# PIN2DMD-v3_0.net
KiCad netlist of a schematic drawn in EAGLE
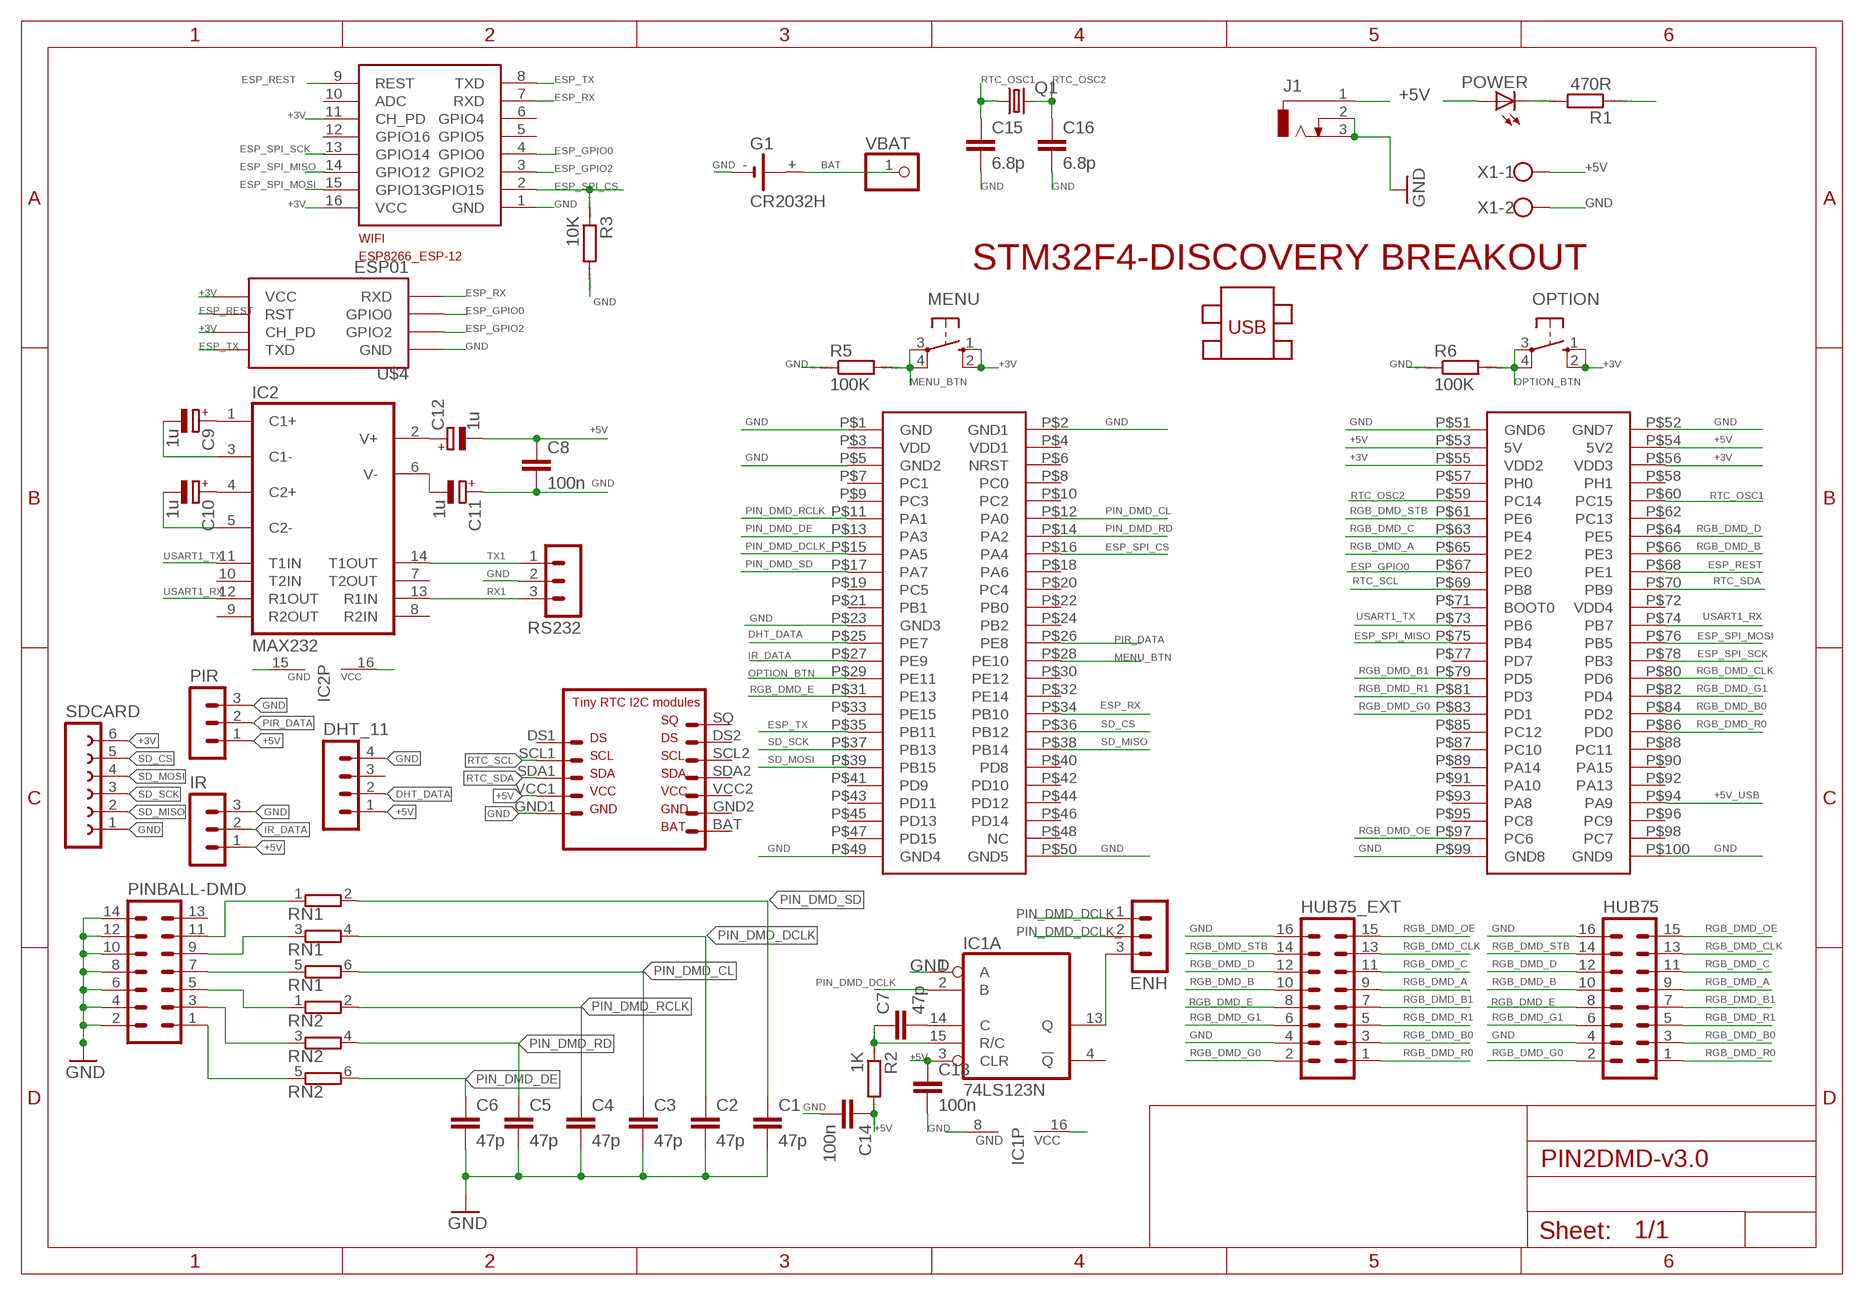
[diagram p0: schematic, sheet 1]

(export (version "E")
  (design (tool "Eeschema 10.0.6"))
  (components
    (comp (ref "C1")
      (value "47p")
      (footprint "eagle-import:C025-024X044")
      (libsource (lib "eagle-import") (part "C-EU025-024X044"))
    )
    (comp (ref "C2")
      (value "47p")
      (footprint "eagle-import:C025-024X044")
      (libsource (lib "eagle-import") (part "C-EU025-024X044"))
    )
    (comp (ref "C3")
      (value "47p")
      (footprint "eagle-import:C025-024X044")
      (libsource (lib "eagle-import") (part "C-EU025-024X044"))
    )
    (comp (ref "C4")
      (value "47p")
      (footprint "eagle-import:C025-024X044")
      (libsource (lib "eagle-import") (part "C-EU025-024X044"))
    )
    (comp (ref "C5")
      (value "47p")
      (footprint "eagle-import:C025-024X044")
      (libsource (lib "eagle-import") (part "C-EU025-024X044"))
    )
    (comp (ref "C6")
      (value "47p")
      (footprint "eagle-import:C025-024X044")
      (libsource (lib "eagle-import") (part "C-EU025-024X044"))
    )
    (comp (ref "C7")
      (value "47p")
      (footprint "eagle-import:C025-024X044")
      (libsource (lib "eagle-import") (part "C-EU025-024X044"))
    )
    (comp (ref "C8")
      (value "100n")
      (footprint "eagle-import:C025-024X044")
      (libsource (lib "eagle-import") (part "C-EU025-024X044"))
    )
    (comp (ref "C9")
      (value "1u")
      (footprint "eagle-import:E2-4")
      (libsource (lib "eagle-import") (part "CPOL-EUE2-4"))
    )
    (comp (ref "C10")
      (value "1u")
      (footprint "eagle-import:E2-4")
      (libsource (lib "eagle-import") (part "CPOL-EUE2-4"))
    )
    (comp (ref "C11")
      (value "1u")
      (footprint "eagle-import:E2-4")
      (libsource (lib "eagle-import") (part "CPOL-EUE2-4"))
    )
    (comp (ref "C12")
      (value "1u")
      (footprint "eagle-import:E2-4")
      (libsource (lib "eagle-import") (part "CPOL-EUE2-4"))
    )
    (comp (ref "C13")
      (value "100n")
      (footprint "eagle-import:C025-024X044")
      (libsource (lib "eagle-import") (part "C-EU025-024X044"))
    )
    (comp (ref "C14")
      (value "100n")
      (footprint "eagle-import:C025-024X044")
      (libsource (lib "eagle-import") (part "C-EU025-024X044"))
    )
    (comp (ref "C15")
      (value "6.8p")
      (footprint "eagle-import:C025-024X044")
      (libsource (lib "eagle-import") (part "C-EU025-024X044"))
    )
    (comp (ref "C16")
      (value "6.8p")
      (footprint "eagle-import:C025-024X044")
      (libsource (lib "eagle-import") (part "C-EU025-024X044"))
    )
    (comp (ref "DHT_11")
      (value "MA04-1")
      (footprint "eagle-import:MA04-1")
      (libsource (lib "eagle-import") (part "MA04-1"))
    )
    (comp (ref "ENH")
      (value "MA03-1")
      (footprint "eagle-import:MA03-1")
      (libsource (lib "eagle-import") (part "MA03-1"))
    )
    (comp (ref "G1")
      (value "CR2032H")
      (footprint "eagle-import:CR2032H")
      (libsource (lib "eagle-import") (part "CR2032H"))
    )
    (comp (ref "HUB75")
      (value "MA08-2")
      (footprint "eagle-import:MA08-2")
      (libsource (lib "eagle-import") (part "MA08-2"))
    )
    (comp (ref "HUB75_EXT")
      (value "MA08-2")
      (footprint "eagle-import:MA08-2")
      (libsource (lib "eagle-import") (part "MA08-2"))
    )
    (comp (ref "IC1")
      (value "74LS123N")
      (footprint "eagle-import:DIL16")
      (libsource (lib "eagle-import") (part "74123NLS"))
    )
    (comp (ref "IC2")
      (value "MAX232")
      (footprint "eagle-import:DIL16")
      (fields (field (name "MF") "MAXIM") (field (name "MPN") "MAX232ACPE+"))
      (libsource (lib "eagle-import") (part "MAX232"))
    )
    (comp (ref "IR")
      (value "MA03-1")
      (footprint "eagle-import:MA03-1")
      (libsource (lib "eagle-import") (part "MA03-1"))
    )
    (comp (ref "J1")
      (value "DCJ0303")
      (footprint "eagle-import:DCJ0303")
      (libsource (lib "eagle-import") (part "DCJ0303"))
    )
    (comp (ref "MENU")
      (value "10-XX")
      (footprint "eagle-import:B3F-10XX")
      (fields (field (name "MPN") "B3F-1000"))
      (libsource (lib "eagle-import") (part "10-XX"))
    )
    (comp (ref "OPTION")
      (value "10-XX")
      (footprint "eagle-import:B3F-10XX")
      (fields (field (name "MPN") "B3F-1000"))
      (libsource (lib "eagle-import") (part "10-XX"))
    )
    (comp (ref "PINBALL-DMD")
      (value "MA07-2")
      (footprint "eagle-import:MA07-2")
      (libsource (lib "eagle-import") (part "MA07-2"))
    )
    (comp (ref "PIR")
      (value "MA03-1")
      (footprint "eagle-import:MA03-1")
      (libsource (lib "eagle-import") (part "MA03-1"))
    )
    (comp (ref "POWER")
      (value "LED3MM")
      (footprint "eagle-import:LED3MM")
      (libsource (lib "eagle-import") (part "LED3MM"))
    )
    (comp (ref "Q1")
      (value "CRYSTALTC38H")
      (footprint "eagle-import:TC38H")
      (libsource (lib "eagle-import") (part "CRYSTALTC38H"))
    )
    (comp (ref "R1")
      (value "470R")
      (footprint "eagle-import:0207_10")
      (libsource (lib "eagle-import") (part "R0207/10"))
    )
    (comp (ref "R2")
      (value "1K")
      (footprint "eagle-import:0207_10")
      (libsource (lib "eagle-import") (part "R0207/10"))
    )
    (comp (ref "R3")
      (value "10K")
      (footprint "eagle-import:0207_10")
      (libsource (lib "eagle-import") (part "R0207/10"))
    )
    (comp (ref "R5")
      (value "100K")
      (footprint "eagle-import:0207_10")
      (libsource (lib "eagle-import") (part "R0207/10"))
    )
    (comp (ref "R6")
      (value "100K")
      (footprint "eagle-import:0207_10")
      (libsource (lib "eagle-import") (part "R0207/10"))
    )
    (comp (ref "RN1")
      (value "E3RP")
      (footprint "eagle-import:SIL6")
      (libsource (lib "eagle-import") (part "E3RP"))
    )
    (comp (ref "RN2")
      (value "E3RP")
      (footprint "eagle-import:SIL6")
      (libsource (lib "eagle-import") (part "E3RP"))
    )
    (comp (ref "RS232")
      (value "MA03-1")
      (footprint "eagle-import:MA03-1")
      (libsource (lib "eagle-import") (part "MA03-1"))
    )
    (comp (ref "SDCARD")
      (value "FE06-1")
      (footprint "eagle-import:FE06")
      (libsource (lib "eagle-import") (part "FE06-1"))
    )
    (comp (ref "U$1")
      (value "STM32F4-DISCOVERY")
      (footprint "eagle-import:STM32F4-DISCOVERY")
      (libsource (lib "eagle-import") (part "STM32F4-DISCOVERY"))
    )
    (comp (ref "U$3")
      (value "RTC")
      (footprint "eagle-import:RTC")
      (libsource (lib "eagle-import") (part "RTC"))
    )
    (comp (ref "U$4")
      (value "ESP01")
      (footprint "eagle-import:ESP01")
      (libsource (lib "eagle-import") (part "ESP01"))
    )
    (comp (ref "VBAT")
      (value "PINHD-1X1")
      (footprint "eagle-import:1X01")
      (libsource (lib "eagle-import") (part "PINHD-1X1"))
    )
    (comp (ref "WIFI")
      (value "ESP8266_ESP-12")
      (footprint "eagle-import:ESP8266-ESP12")
      (libsource (lib "eagle-import") (part "ESP8266_ESP-12"))
    )
    (comp (ref "X1")
      (value "W237-102")
      (footprint "eagle-import:W237-102")
      (fields (field (name "MPN") "237-102"))
      (libsource (lib "eagle-import") (part "W237-102"))
    )
  )
  (nets
    (net (code "1") (name "+3V") (class "Default")
      (node (ref "MENU") (pin "1") (pinfunction "S_1") (pintype "passive"))
      (node (ref "MENU") (pin "2") (pinfunction "S1_2") (pintype "passive"))
      (node (ref "OPTION") (pin "1") (pinfunction "S_1") (pintype "passive"))
      (node (ref "OPTION") (pin "2") (pinfunction "S1_2") (pintype "passive"))
      (node (ref "SDCARD") (pin "6") (pinfunction "6_6") (pintype "passive"))
      (node (ref "U$1") (pin "P$55") (pinfunction "VDD2_P$55") (pintype "bidirectional"))
      (node (ref "U$1") (pin "P$56") (pinfunction "VDD3_P$56") (pintype "bidirectional"))
      (node (ref "U$4") (pin "CH_PD") (pinfunction "CH_PD_CH_PD") (pintype "bidirectional"))
      (node (ref "U$4") (pin "VCC") (pinfunction "VCC_VCC") (pintype "bidirectional"))
      (node (ref "WIFI") (pin "11") (pinfunction "CH_PD_11") (pintype "bidirectional"))
      (node (ref "WIFI") (pin "16") (pinfunction "VCC_16") (pintype "bidirectional"))
    )
    (net (code "2") (name "+5V") (class "Default")
      (node (ref "C12") (pin "-") (pinfunction "-_-") (pintype "passive"))
      (node (ref "C13") (pin "1") (pinfunction "1_1") (pintype "passive"))
      (node (ref "C14") (pin "1") (pinfunction "1_1") (pintype "passive"))
      (node (ref "C8") (pin "1") (pinfunction "1_1") (pintype "passive"))
      (node (ref "DHT_11") (pin "1") (pinfunction "1_1") (pintype "passive"))
      (node (ref "IC1") (pin "16") (pinfunction "VCC_16") (pintype "power_in"))
      (node (ref "IC1") (pin "3") (pinfunction "CLR_3") (pintype "input"))
      (node (ref "IC2") (pin "16") (pinfunction "VCC_16") (pintype "power_in"))
      (node (ref "IR") (pin "1") (pinfunction "1_1") (pintype "passive"))
      (node (ref "J1") (pin "1") (pinfunction "1_1") (pintype "passive"))
      (node (ref "PIR") (pin "1") (pinfunction "1_1") (pintype "passive"))
      (node (ref "POWER") (pin "A") (pinfunction "A_A") (pintype "passive"))
      (node (ref "R2") (pin "2") (pinfunction "2_2") (pintype "passive"))
      (node (ref "U$1") (pin "P$53") (pinfunction "5V_P$53") (pintype "bidirectional"))
      (node (ref "U$1") (pin "P$54") (pinfunction "5V2_P$54") (pintype "bidirectional"))
      (node (ref "U$3") (pin "VCC1") (pinfunction "VCC1_VCC1") (pintype "passive"))
      (node (ref "X1") (pin "1") (pinfunction "KL_1") (pintype "passive"))
    )
    (net (code "3") (name "/+5V_USB") (class "Default")
      (node (ref "U$1") (pin "P$94") (pinfunction "PA9_P$94") (pintype "bidirectional"))
    )
    (net (code "4") (name "/BAT") (class "Default")
      (node (ref "G1") (pin "+") (pinfunction "+_+") (pintype "passive"))
      (node (ref "VBAT") (pin "1") (pinfunction "1_1") (pintype "passive"))
    )
    (net (code "5") (name "/ESP_GPIO0") (class "Default")
      (node (ref "U$1") (pin "P$67") (pinfunction "PE0_P$67") (pintype "bidirectional"))
      (node (ref "U$4") (pin "GPIO0") (pinfunction "GPIO0_GPIO0") (pintype "bidirectional"))
      (node (ref "WIFI") (pin "4") (pinfunction "GPIO0_4") (pintype "bidirectional"))
    )
    (net (code "6") (name "/ESP_GPIO2") (class "Default")
      (node (ref "U$4") (pin "GPIO2") (pinfunction "GPIO2_GPIO2") (pintype "bidirectional"))
      (node (ref "WIFI") (pin "3") (pinfunction "GPIO2_3") (pintype "bidirectional"))
    )
    (net (code "7") (name "/ESP_REST") (class "Default")
      (node (ref "U$1") (pin "P$68") (pinfunction "PE1_P$68") (pintype "bidirectional"))
      (node (ref "U$4") (pin "RST") (pinfunction "RST_RST") (pintype "bidirectional"))
      (node (ref "WIFI") (pin "9") (pinfunction "REST_9") (pintype "bidirectional"))
    )
    (net (code "8") (name "/ESP_RX") (class "Default")
      (node (ref "U$1") (pin "P$34") (pinfunction "PB10_P$34") (pintype "bidirectional"))
      (node (ref "U$4") (pin "RX") (pinfunction "RXD_RX") (pintype "bidirectional"))
      (node (ref "WIFI") (pin "7") (pinfunction "RXD_7") (pintype "bidirectional"))
    )
    (net (code "9") (name "/ESP_SPI_CS") (class "Default")
      (node (ref "R3") (pin "1") (pinfunction "1_1") (pintype "passive"))
      (node (ref "U$1") (pin "P$16") (pinfunction "PA4_P$16") (pintype "bidirectional"))
      (node (ref "WIFI") (pin "2") (pinfunction "GPIO15_2") (pintype "bidirectional"))
    )
    (net (code "10") (name "/ESP_SPI_MISO") (class "Default")
      (node (ref "U$1") (pin "P$75") (pinfunction "PB4_P$75") (pintype "bidirectional"))
      (node (ref "WIFI") (pin "14") (pinfunction "GPIO12_14") (pintype "bidirectional"))
    )
    (net (code "11") (name "/ESP_SPI_MOSI") (class "Default")
      (node (ref "U$1") (pin "P$76") (pinfunction "PB5_P$76") (pintype "bidirectional"))
      (node (ref "WIFI") (pin "15") (pinfunction "GPIO13_15") (pintype "bidirectional"))
    )
    (net (code "12") (name "/ESP_SPI_SCK") (class "Default")
      (node (ref "U$1") (pin "P$78") (pinfunction "PB3_P$78") (pintype "bidirectional"))
      (node (ref "WIFI") (pin "13") (pinfunction "GPIO14_13") (pintype "bidirectional"))
    )
    (net (code "13") (name "/ESP_TX") (class "Default")
      (node (ref "U$1") (pin "P$35") (pinfunction "PB11_P$35") (pintype "bidirectional"))
      (node (ref "U$4") (pin "TX") (pinfunction "TXD_TX") (pintype "bidirectional"))
      (node (ref "WIFI") (pin "8") (pinfunction "TXD_8") (pintype "bidirectional"))
    )
    (net (code "14") (name "/MENU_BTN") (class "Default")
      (node (ref "MENU") (pin "3") (pinfunction "P_3") (pintype "passive"))
      (node (ref "MENU") (pin "4") (pinfunction "P1_4") (pintype "passive"))
      (node (ref "R5") (pin "2") (pinfunction "2_2") (pintype "passive"))
      (node (ref "U$1") (pin "P$28") (pinfunction "PE10_P$28") (pintype "bidirectional"))
    )
    (net (code "15") (name "/OPTION_BTN") (class "Default")
      (node (ref "OPTION") (pin "3") (pinfunction "P_3") (pintype "passive"))
      (node (ref "OPTION") (pin "4") (pinfunction "P1_4") (pintype "passive"))
      (node (ref "R6") (pin "2") (pinfunction "2_2") (pintype "passive"))
      (node (ref "U$1") (pin "P$29") (pinfunction "PE11_P$29") (pintype "bidirectional"))
    )
    (net (code "16") (name "/PIN_DMD_DCLK_") (class "Default")
      (node (ref "ENH") (pin "2") (pinfunction "2_2") (pintype "passive"))
      (node (ref "U$1") (pin "P$15") (pinfunction "PA5_P$15") (pintype "bidirectional"))
    )
    (net (code "17") (name "/RGB_DMD_A") (class "Default")
      (node (ref "HUB75") (pin "9") (pinfunction "9_9") (pintype "passive"))
      (node (ref "HUB75_EXT") (pin "9") (pinfunction "9_9") (pintype "passive"))
      (node (ref "U$1") (pin "P$65") (pinfunction "PE2_P$65") (pintype "bidirectional"))
    )
    (net (code "18") (name "/RGB_DMD_B") (class "Default")
      (node (ref "HUB75") (pin "10") (pinfunction "10_10") (pintype "passive"))
      (node (ref "HUB75_EXT") (pin "10") (pinfunction "10_10") (pintype "passive"))
      (node (ref "U$1") (pin "P$66") (pinfunction "PE3_P$66") (pintype "bidirectional"))
    )
    (net (code "19") (name "/RGB_DMD_B0") (class "Default")
      (node (ref "HUB75") (pin "3") (pinfunction "3_3") (pintype "passive"))
      (node (ref "HUB75_EXT") (pin "3") (pinfunction "3_3") (pintype "passive"))
      (node (ref "U$1") (pin "P$84") (pinfunction "PD2_P$84") (pintype "bidirectional"))
    )
    (net (code "20") (name "/RGB_DMD_B1") (class "Default")
      (node (ref "HUB75") (pin "7") (pinfunction "7_7") (pintype "passive"))
      (node (ref "HUB75_EXT") (pin "7") (pinfunction "7_7") (pintype "passive"))
      (node (ref "U$1") (pin "P$79") (pinfunction "PD5_P$79") (pintype "bidirectional"))
    )
    (net (code "21") (name "/RGB_DMD_C") (class "Default")
      (node (ref "HUB75") (pin "11") (pinfunction "11_11") (pintype "passive"))
      (node (ref "HUB75_EXT") (pin "11") (pinfunction "11_11") (pintype "passive"))
      (node (ref "U$1") (pin "P$63") (pinfunction "PE4_P$63") (pintype "bidirectional"))
    )
    (net (code "22") (name "/RGB_DMD_CLK") (class "Default")
      (node (ref "HUB75") (pin "13") (pinfunction "13_13") (pintype "passive"))
      (node (ref "HUB75_EXT") (pin "13") (pinfunction "13_13") (pintype "passive"))
      (node (ref "U$1") (pin "P$80") (pinfunction "PD6_P$80") (pintype "bidirectional"))
    )
    (net (code "23") (name "/RGB_DMD_D") (class "Default")
      (node (ref "HUB75") (pin "12") (pinfunction "12_12") (pintype "passive"))
      (node (ref "HUB75_EXT") (pin "12") (pinfunction "12_12") (pintype "passive"))
      (node (ref "U$1") (pin "P$64") (pinfunction "PE5_P$64") (pintype "bidirectional"))
    )
    (net (code "24") (name "/RGB_DMD_E") (class "Default")
      (node (ref "HUB75") (pin "8") (pinfunction "8_8") (pintype "passive"))
      (node (ref "HUB75_EXT") (pin "8") (pinfunction "8_8") (pintype "passive"))
      (node (ref "U$1") (pin "P$31") (pinfunction "PE13_P$31") (pintype "bidirectional"))
    )
    (net (code "25") (name "/RGB_DMD_G0") (class "Default")
      (node (ref "HUB75") (pin "2") (pinfunction "2_2") (pintype "passive"))
      (node (ref "HUB75_EXT") (pin "2") (pinfunction "2_2") (pintype "passive"))
      (node (ref "U$1") (pin "P$83") (pinfunction "PD1_P$83") (pintype "bidirectional"))
    )
    (net (code "26") (name "/RGB_DMD_G1") (class "Default")
      (node (ref "HUB75") (pin "6") (pinfunction "6_6") (pintype "passive"))
      (node (ref "HUB75_EXT") (pin "6") (pinfunction "6_6") (pintype "passive"))
      (node (ref "U$1") (pin "P$82") (pinfunction "PD4_P$82") (pintype "bidirectional"))
    )
    (net (code "27") (name "/RGB_DMD_OE") (class "Default")
      (node (ref "HUB75") (pin "15") (pinfunction "15_15") (pintype "passive"))
      (node (ref "HUB75_EXT") (pin "15") (pinfunction "15_15") (pintype "passive"))
      (node (ref "U$1") (pin "P$97") (pinfunction "PC6_P$97") (pintype "bidirectional"))
    )
    (net (code "28") (name "/RGB_DMD_R0") (class "Default")
      (node (ref "HUB75") (pin "1") (pinfunction "1_1") (pintype "passive"))
      (node (ref "HUB75_EXT") (pin "1") (pinfunction "1_1") (pintype "passive"))
      (node (ref "U$1") (pin "P$86") (pinfunction "PD0_P$86") (pintype "bidirectional"))
    )
    (net (code "29") (name "/RGB_DMD_R1") (class "Default")
      (node (ref "HUB75") (pin "5") (pinfunction "5_5") (pintype "passive"))
      (node (ref "HUB75_EXT") (pin "5") (pinfunction "5_5") (pintype "passive"))
      (node (ref "U$1") (pin "P$81") (pinfunction "PD3_P$81") (pintype "bidirectional"))
    )
    (net (code "30") (name "/RGB_DMD_STB") (class "Default")
      (node (ref "HUB75") (pin "14") (pinfunction "14_14") (pintype "passive"))
      (node (ref "HUB75_EXT") (pin "14") (pinfunction "14_14") (pintype "passive"))
      (node (ref "U$1") (pin "P$61") (pinfunction "PE6_P$61") (pintype "bidirectional"))
    )
    (net (code "31") (name "/RTC_OSC1") (class "Default")
      (node (ref "C15") (pin "1") (pinfunction "1_1") (pintype "passive"))
      (node (ref "Q1") (pin "1") (pinfunction "1_1") (pintype "passive"))
      (node (ref "U$1") (pin "P$60") (pinfunction "PC15_P$60") (pintype "bidirectional"))
    )
    (net (code "32") (name "/RTC_OSC2") (class "Default")
      (node (ref "C16") (pin "1") (pinfunction "1_1") (pintype "passive"))
      (node (ref "Q1") (pin "2") (pinfunction "2_2") (pintype "passive"))
      (node (ref "U$1") (pin "P$59") (pinfunction "PC14_P$59") (pintype "bidirectional"))
    )
    (net (code "33") (name "/RX1") (class "Default")
      (node (ref "IC2") (pin "13") (pinfunction "R1IN_13") (pintype "input"))
      (node (ref "RS232") (pin "3") (pinfunction "3_3") (pintype "passive"))
    )
    (net (code "34") (name "/TX1") (class "Default")
      (node (ref "IC2") (pin "14") (pinfunction "T1OUT_14") (pintype "output"))
      (node (ref "RS232") (pin "1") (pinfunction "1_1") (pintype "passive"))
    )
    (net (code "35") (name "/USART1_RX") (class "Default")
      (node (ref "IC2") (pin "12") (pinfunction "R1OUT_12") (pintype "output"))
      (node (ref "U$1") (pin "P$74") (pinfunction "PB7_P$74") (pintype "bidirectional"))
    )
    (net (code "36") (name "/USART1_TX") (class "Default")
      (node (ref "IC2") (pin "11") (pinfunction "T1IN_11") (pintype "input"))
      (node (ref "U$1") (pin "P$73") (pinfunction "PB6_P$73") (pintype "bidirectional"))
    )
    (net (code "37") (name "DHT_DATA") (class "Default")
      (node (ref "DHT_11") (pin "2") (pinfunction "2_2") (pintype "passive"))
      (node (ref "U$1") (pin "P$25") (pinfunction "PE7_P$25") (pintype "bidirectional"))
    )
    (net (code "38") (name "GND") (class "Default")
      (node (ref "C1") (pin "2") (pinfunction "2_2") (pintype "passive"))
      (node (ref "C11") (pin "+") (pinfunction "+_+") (pintype "passive"))
      (node (ref "C13") (pin "2") (pinfunction "2_2") (pintype "passive"))
      (node (ref "C14") (pin "2") (pinfunction "2_2") (pintype "passive"))
      (node (ref "C15") (pin "2") (pinfunction "2_2") (pintype "passive"))
      (node (ref "C16") (pin "2") (pinfunction "2_2") (pintype "passive"))
      (node (ref "C2") (pin "2") (pinfunction "2_2") (pintype "passive"))
      (node (ref "C3") (pin "2") (pinfunction "2_2") (pintype "passive"))
      (node (ref "C4") (pin "2") (pinfunction "2_2") (pintype "passive"))
      (node (ref "C5") (pin "2") (pinfunction "2_2") (pintype "passive"))
      (node (ref "C6") (pin "2") (pinfunction "2_2") (pintype "passive"))
      (node (ref "C8") (pin "2") (pinfunction "2_2") (pintype "passive"))
      (node (ref "DHT_11") (pin "4") (pinfunction "4_4") (pintype "passive"))
      (node (ref "G1") (pin "-") (pinfunction "-_-") (pintype "passive"))
      (node (ref "HUB75") (pin "16") (pinfunction "16_16") (pintype "passive"))
      (node (ref "HUB75") (pin "4") (pinfunction "4_4") (pintype "passive"))
      (node (ref "HUB75_EXT") (pin "16") (pinfunction "16_16") (pintype "passive"))
      (node (ref "HUB75_EXT") (pin "4") (pinfunction "4_4") (pintype "passive"))
      (node (ref "IC1") (pin "1") (pinfunction "A_1") (pintype "input"))
      (node (ref "IC1") (pin "8") (pinfunction "GND_8") (pintype "power_in"))
      (node (ref "IC2") (pin "15") (pinfunction "GND_15") (pintype "power_in"))
      (node (ref "IR") (pin "3") (pinfunction "3_3") (pintype "passive"))
      (node (ref "J1") (pin "2") (pinfunction "2_2") (pintype "passive"))
      (node (ref "J1") (pin "3") (pinfunction "3_3") (pintype "passive"))
      (node (ref "PINBALL-DMD") (pin "10") (pinfunction "10_10") (pintype "passive"))
      (node (ref "PINBALL-DMD") (pin "12") (pinfunction "12_12") (pintype "passive"))
      (node (ref "PINBALL-DMD") (pin "14") (pinfunction "14_14") (pintype "passive"))
      (node (ref "PINBALL-DMD") (pin "2") (pinfunction "2_2") (pintype "passive"))
      (node (ref "PINBALL-DMD") (pin "4") (pinfunction "4_4") (pintype "passive"))
      (node (ref "PINBALL-DMD") (pin "6") (pinfunction "6_6") (pintype "passive"))
      (node (ref "PINBALL-DMD") (pin "8") (pinfunction "8_8") (pintype "passive"))
      (node (ref "PIR") (pin "3") (pinfunction "3_3") (pintype "passive"))
      (node (ref "R1") (pin "1") (pinfunction "1_1") (pintype "passive"))
      (node (ref "R3") (pin "2") (pinfunction "2_2") (pintype "passive"))
      (node (ref "R5") (pin "1") (pinfunction "1_1") (pintype "passive"))
      (node (ref "R6") (pin "1") (pinfunction "1_1") (pintype "passive"))
      (node (ref "RS232") (pin "2") (pinfunction "2_2") (pintype "passive"))
      (node (ref "SDCARD") (pin "1") (pinfunction "1_1") (pintype "passive"))
      (node (ref "U$1") (pin "P$1") (pinfunction "GND_P$1") (pintype "bidirectional"))
      (node (ref "U$1") (pin "P$100") (pinfunction "GND9_P$100") (pintype "bidirectional"))
      (node (ref "U$1") (pin "P$2") (pinfunction "GND1_P$2") (pintype "bidirectional"))
      (node (ref "U$1") (pin "P$23") (pinfunction "GND3_P$23") (pintype "bidirectional"))
      (node (ref "U$1") (pin "P$49") (pinfunction "GND4_P$49") (pintype "bidirectional"))
      (node (ref "U$1") (pin "P$5") (pinfunction "GND2_P$5") (pintype "bidirectional"))
      (node (ref "U$1") (pin "P$50") (pinfunction "GND5_P$50") (pintype "bidirectional"))
      (node (ref "U$1") (pin "P$51") (pinfunction "GND6_P$51") (pintype "bidirectional"))
      (node (ref "U$1") (pin "P$52") (pinfunction "GND7_P$52") (pintype "bidirectional"))
      (node (ref "U$1") (pin "P$99") (pinfunction "GND8_P$99") (pintype "bidirectional"))
      (node (ref "U$3") (pin "GND1") (pinfunction "GND1_GND1") (pintype "passive"))
      (node (ref "U$4") (pin "GND") (pinfunction "GND_GND") (pintype "bidirectional"))
      (node (ref "WIFI") (pin "1") (pinfunction "GND_1") (pintype "bidirectional"))
      (node (ref "X1") (pin "2") (pinfunction "KL_2") (pintype "passive"))
    )
    (net (code "39") (name "IR_DATA") (class "Default")
      (node (ref "IR") (pin "2") (pinfunction "2_2") (pintype "passive"))
      (node (ref "U$1") (pin "P$27") (pinfunction "PE9_P$27") (pintype "bidirectional"))
    )
    (net (code "40") (name "Net-(IC1A-C)") (class "Default")
      (node (ref "C7") (pin "2") (pinfunction "2_2") (pintype "passive"))
      (node (ref "IC1") (pin "14") (pinfunction "C_14") (pintype "input"))
    )
    (net (code "41") (name "Net-(IC1A-Q)") (class "Default")
      (node (ref "ENH") (pin "3") (pinfunction "3_3") (pintype "passive"))
      (node (ref "IC1") (pin "13") (pinfunction "Q_13") (pintype "output"))
    )
    (net (code "42") (name "Net-(IC1A-R{slash}C)") (class "Default")
      (node (ref "C7") (pin "1") (pinfunction "1_1") (pintype "passive"))
      (node (ref "IC1") (pin "15") (pinfunction "R/C_15") (pintype "input"))
      (node (ref "R2") (pin "1") (pinfunction "1_1") (pintype "passive"))
    )
    (net (code "43") (name "Net-(IC2A-C1+)") (class "Default")
      (node (ref "C9") (pin "+") (pinfunction "+_+") (pintype "passive"))
      (node (ref "IC2") (pin "1") (pinfunction "C1+_1") (pintype "bidirectional"))
    )
    (net (code "44") (name "Net-(IC2A-C1-)") (class "Default")
      (node (ref "C9") (pin "-") (pinfunction "-_-") (pintype "passive"))
      (node (ref "IC2") (pin "3") (pinfunction "C1-_3") (pintype "bidirectional"))
    )
    (net (code "45") (name "Net-(IC2A-C2+)") (class "Default")
      (node (ref "C10") (pin "+") (pinfunction "+_+") (pintype "passive"))
      (node (ref "IC2") (pin "4") (pinfunction "C2+_4") (pintype "bidirectional"))
    )
    (net (code "46") (name "Net-(IC2A-C2-)") (class "Default")
      (node (ref "C10") (pin "-") (pinfunction "-_-") (pintype "passive"))
      (node (ref "IC2") (pin "5") (pinfunction "C2-_5") (pintype "bidirectional"))
    )
    (net (code "47") (name "Net-(IC2A-V+)") (class "Default")
      (node (ref "C12") (pin "+") (pinfunction "+_+") (pintype "passive"))
      (node (ref "IC2") (pin "2") (pinfunction "V+_2") (pintype "bidirectional"))
    )
    (net (code "48") (name "Net-(IC2A-V-)") (class "Default")
      (node (ref "C11") (pin "-") (pinfunction "-_-") (pintype "passive"))
      (node (ref "IC2") (pin "6") (pinfunction "V-_6") (pintype "bidirectional"))
    )
    (net (code "49") (name "Net-(PINBALL-DMD-Pad5)") (class "Default")
      (node (ref "PINBALL-DMD") (pin "5") (pinfunction "5_5") (pintype "passive"))
      (node (ref "RN2") (pin "1") (pinfunction "1_1") (pintype "passive"))
    )
    (net (code "50") (name "Net-(PINBALL-DMD-Pad11)") (class "Default")
      (node (ref "PINBALL-DMD") (pin "11") (pinfunction "11_11") (pintype "passive"))
      (node (ref "RN1") (pin "1") (pinfunction "1_1") (pintype "passive"))
    )
    (net (code "51") (name "Net-(POWER-C)") (class "Default")
      (node (ref "POWER") (pin "K") (pinfunction "C_K") (pintype "passive"))
      (node (ref "R1") (pin "2") (pinfunction "2_2") (pintype "passive"))
    )
    (net (code "52") (name "Net-(RN1B-1)") (class "Default")
      (node (ref "PINBALL-DMD") (pin "9") (pinfunction "9_9") (pintype "passive"))
      (node (ref "RN1") (pin "3") (pinfunction "1_3") (pintype "passive"))
    )
    (net (code "53") (name "Net-(RN1C-1)") (class "Default")
      (node (ref "PINBALL-DMD") (pin "7") (pinfunction "7_7") (pintype "passive"))
      (node (ref "RN1") (pin "5") (pinfunction "1_5") (pintype "passive"))
    )
    (net (code "54") (name "Net-(RN2B-1)") (class "Default")
      (node (ref "PINBALL-DMD") (pin "3") (pinfunction "3_3") (pintype "passive"))
      (node (ref "RN2") (pin "3") (pinfunction "1_3") (pintype "passive"))
    )
    (net (code "55") (name "Net-(RN2C-1)") (class "Default")
      (node (ref "PINBALL-DMD") (pin "1") (pinfunction "1_1") (pintype "passive"))
      (node (ref "RN2") (pin "5") (pinfunction "1_5") (pintype "passive"))
    )
    (net (code "56") (name "PIN_DMD_CL") (class "Default")
      (node (ref "C3") (pin "1") (pinfunction "1_1") (pintype "passive"))
      (node (ref "RN1") (pin "6") (pinfunction "2_6") (pintype "passive"))
      (node (ref "U$1") (pin "P$12") (pinfunction "PA0_P$12") (pintype "bidirectional"))
    )
    (net (code "57") (name "PIN_DMD_DCLK") (class "Default")
      (node (ref "C2") (pin "1") (pinfunction "1_1") (pintype "passive"))
      (node (ref "ENH") (pin "1") (pinfunction "1_1") (pintype "passive"))
      (node (ref "IC1") (pin "2") (pinfunction "B_2") (pintype "input"))
      (node (ref "RN1") (pin "4") (pinfunction "2_4") (pintype "passive"))
    )
    (net (code "58") (name "PIN_DMD_DE") (class "Default")
      (node (ref "C6") (pin "1") (pinfunction "1_1") (pintype "passive"))
      (node (ref "RN2") (pin "6") (pinfunction "2_6") (pintype "passive"))
      (node (ref "U$1") (pin "P$13") (pinfunction "PA3_P$13") (pintype "bidirectional"))
    )
    (net (code "59") (name "PIN_DMD_RCLK") (class "Default")
      (node (ref "C4") (pin "1") (pinfunction "1_1") (pintype "passive"))
      (node (ref "RN2") (pin "2") (pinfunction "2_2") (pintype "passive"))
      (node (ref "U$1") (pin "P$11") (pinfunction "PA1_P$11") (pintype "bidirectional"))
    )
    (net (code "60") (name "PIN_DMD_RD") (class "Default")
      (node (ref "C5") (pin "1") (pinfunction "1_1") (pintype "passive"))
      (node (ref "RN2") (pin "4") (pinfunction "2_4") (pintype "passive"))
      (node (ref "U$1") (pin "P$14") (pinfunction "PA2_P$14") (pintype "bidirectional"))
    )
    (net (code "61") (name "PIN_DMD_SD") (class "Default")
      (node (ref "C1") (pin "1") (pinfunction "1_1") (pintype "passive"))
      (node (ref "RN1") (pin "2") (pinfunction "2_2") (pintype "passive"))
      (node (ref "U$1") (pin "P$17") (pinfunction "PA7_P$17") (pintype "bidirectional"))
    )
    (net (code "62") (name "PIR_DATA") (class "Default")
      (node (ref "PIR") (pin "2") (pinfunction "2_2") (pintype "passive"))
      (node (ref "U$1") (pin "P$26") (pinfunction "PE8_P$26") (pintype "bidirectional"))
    )
    (net (code "63") (name "RTC_SCL") (class "Default")
      (node (ref "U$1") (pin "P$69") (pinfunction "PB8_P$69") (pintype "bidirectional"))
      (node (ref "U$3") (pin "SCL1") (pinfunction "SCL1_SCL1") (pintype "passive"))
    )
    (net (code "64") (name "RTC_SDA") (class "Default")
      (node (ref "U$1") (pin "P$70") (pinfunction "PB9_P$70") (pintype "bidirectional"))
      (node (ref "U$3") (pin "SDA1") (pinfunction "SDA1_SDA1") (pintype "passive"))
    )
    (net (code "65") (name "SD_CS") (class "Default")
      (node (ref "SDCARD") (pin "5") (pinfunction "5_5") (pintype "passive"))
      (node (ref "U$1") (pin "P$36") (pinfunction "PB12_P$36") (pintype "bidirectional"))
    )
    (net (code "66") (name "SD_MISO") (class "Default")
      (node (ref "SDCARD") (pin "2") (pinfunction "2_2") (pintype "passive"))
      (node (ref "U$1") (pin "P$38") (pinfunction "PB14_P$38") (pintype "bidirectional"))
    )
    (net (code "67") (name "SD_MOSI") (class "Default")
      (node (ref "SDCARD") (pin "4") (pinfunction "4_4") (pintype "passive"))
      (node (ref "U$1") (pin "P$39") (pinfunction "PB15_P$39") (pintype "bidirectional"))
    )
    (net (code "68") (name "SD_SCK") (class "Default")
      (node (ref "SDCARD") (pin "3") (pinfunction "3_3") (pintype "passive"))
      (node (ref "U$1") (pin "P$37") (pinfunction "PB13_P$37") (pintype "bidirectional"))
    )
    (net (code "69") (name "unconnected-(DHT_11-Pad3)") (class "Default")
      (node (ref "DHT_11") (pin "3") (pinfunction "3_3") (pintype "passive"))
    )
    (net (code "70") (name "unconnected-(G1-+-Pad+@1)") (class "Default")
      (node (ref "G1") (pin "+@1") (pinfunction "+_+@1") (pintype "passive"))
    )
    (net (code "71") (name "unconnected-(IC1A-~{Q}-Pad4)") (class "Default")
      (node (ref "IC1") (pin "4") (pinfunction "~{Q}_4") (pintype "output"))
    )
    (net (code "72") (name "unconnected-(IC2A-R2IN-Pad8)") (class "Default")
      (node (ref "IC2") (pin "8") (pinfunction "R2IN_8") (pintype "input"))
    )
    (net (code "73") (name "unconnected-(IC2A-R2OUT-Pad9)") (class "Default")
      (node (ref "IC2") (pin "9") (pinfunction "R2OUT_9") (pintype "output"))
    )
    (net (code "74") (name "unconnected-(IC2A-T2IN-Pad10)") (class "Default")
      (node (ref "IC2") (pin "10") (pinfunction "T2IN_10") (pintype "input"))
    )
    (net (code "75") (name "unconnected-(IC2A-T2OUT-Pad7)") (class "Default")
      (node (ref "IC2") (pin "7") (pinfunction "T2OUT_7") (pintype "output"))
    )
    (net (code "76") (name "unconnected-(PINBALL-DMD-Pad13)") (class "Default")
      (node (ref "PINBALL-DMD") (pin "13") (pinfunction "13_13") (pintype "passive"))
    )
    (net (code "77") (name "unconnected-(U$1-BOOT0-PadP$71)") (class "Default")
      (node (ref "U$1") (pin "P$71") (pinfunction "BOOT0_P$71") (pintype "bidirectional"))
    )
    (net (code "78") (name "unconnected-(U$1-NC-PadP$48)") (class "Default")
      (node (ref "U$1") (pin "P$48") (pinfunction "NC_P$48") (pintype "bidirectional"))
    )
    (net (code "79") (name "unconnected-(U$1-NRST-PadP$6)") (class "Default")
      (node (ref "U$1") (pin "P$6") (pinfunction "NRST_P$6") (pintype "bidirectional"))
    )
    (net (code "80") (name "unconnected-(U$1-PA6-PadP$18)") (class "Default")
      (node (ref "U$1") (pin "P$18") (pinfunction "PA6_P$18") (pintype "bidirectional"))
    )
    (net (code "81") (name "unconnected-(U$1-PA8-PadP$93)") (class "Default")
      (node (ref "U$1") (pin "P$93") (pinfunction "PA8_P$93") (pintype "bidirectional"))
    )
    (net (code "82") (name "unconnected-(U$1-PA10-PadP$91)") (class "Default")
      (node (ref "U$1") (pin "P$91") (pinfunction "PA10_P$91") (pintype "bidirectional"))
    )
    (net (code "83") (name "unconnected-(U$1-PA13-PadP$92)") (class "Default")
      (node (ref "U$1") (pin "P$92") (pinfunction "PA13_P$92") (pintype "bidirectional"))
    )
    (net (code "84") (name "unconnected-(U$1-PA14-PadP$89)") (class "Default")
      (node (ref "U$1") (pin "P$89") (pinfunction "PA14_P$89") (pintype "bidirectional"))
    )
    (net (code "85") (name "unconnected-(U$1-PA15-PadP$90)") (class "Default")
      (node (ref "U$1") (pin "P$90") (pinfunction "PA15_P$90") (pintype "bidirectional"))
    )
    (net (code "86") (name "unconnected-(U$1-PB0-PadP$22)") (class "Default")
      (node (ref "U$1") (pin "P$22") (pinfunction "PB0_P$22") (pintype "bidirectional"))
    )
    (net (code "87") (name "unconnected-(U$1-PB1-PadP$21)") (class "Default")
      (node (ref "U$1") (pin "P$21") (pinfunction "PB1_P$21") (pintype "bidirectional"))
    )
    (net (code "88") (name "unconnected-(U$1-PB2-PadP$24)") (class "Default")
      (node (ref "U$1") (pin "P$24") (pinfunction "PB2_P$24") (pintype "bidirectional"))
    )
    (net (code "89") (name "unconnected-(U$1-PC0-PadP$8)") (class "Default")
      (node (ref "U$1") (pin "P$8") (pinfunction "PC0_P$8") (pintype "bidirectional"))
    )
    (net (code "90") (name "unconnected-(U$1-PC1-PadP$7)") (class "Default")
      (node (ref "U$1") (pin "P$7") (pinfunction "PC1_P$7") (pintype "bidirectional"))
    )
    (net (code "91") (name "unconnected-(U$1-PC2-PadP$10)") (class "Default")
      (node (ref "U$1") (pin "P$10") (pinfunction "PC2_P$10") (pintype "bidirectional"))
    )
    (net (code "92") (name "unconnected-(U$1-PC3-PadP$9)") (class "Default")
      (node (ref "U$1") (pin "P$9") (pinfunction "PC3_P$9") (pintype "bidirectional"))
    )
    (net (code "93") (name "unconnected-(U$1-PC4-PadP$20)") (class "Default")
      (node (ref "U$1") (pin "P$20") (pinfunction "PC4_P$20") (pintype "bidirectional"))
    )
    (net (code "94") (name "unconnected-(U$1-PC5-PadP$19)") (class "Default")
      (node (ref "U$1") (pin "P$19") (pinfunction "PC5_P$19") (pintype "bidirectional"))
    )
    (net (code "95") (name "unconnected-(U$1-PC7-PadP$98)") (class "Default")
      (node (ref "U$1") (pin "P$98") (pinfunction "PC7_P$98") (pintype "bidirectional"))
    )
    (net (code "96") (name "unconnected-(U$1-PC8-PadP$95)") (class "Default")
      (node (ref "U$1") (pin "P$95") (pinfunction "PC8_P$95") (pintype "bidirectional"))
    )
    (net (code "97") (name "unconnected-(U$1-PC9-PadP$96)") (class "Default")
      (node (ref "U$1") (pin "P$96") (pinfunction "PC9_P$96") (pintype "bidirectional"))
    )
    (net (code "98") (name "unconnected-(U$1-PC10-PadP$87)") (class "Default")
      (node (ref "U$1") (pin "P$87") (pinfunction "PC10_P$87") (pintype "bidirectional"))
    )
    (net (code "99") (name "unconnected-(U$1-PC11-PadP$88)") (class "Default")
      (node (ref "U$1") (pin "P$88") (pinfunction "PC11_P$88") (pintype "bidirectional"))
    )
    (net (code "100") (name "unconnected-(U$1-PC12-PadP$85)") (class "Default")
      (node (ref "U$1") (pin "P$85") (pinfunction "PC12_P$85") (pintype "bidirectional"))
    )
    (net (code "101") (name "unconnected-(U$1-PC13-PadP$62)") (class "Default")
      (node (ref "U$1") (pin "P$62") (pinfunction "PC13_P$62") (pintype "bidirectional"))
    )
    (net (code "102") (name "unconnected-(U$1-PD7-PadP$77)") (class "Default")
      (node (ref "U$1") (pin "P$77") (pinfunction "PD7_P$77") (pintype "bidirectional"))
    )
    (net (code "103") (name "unconnected-(U$1-PD8-PadP$40)") (class "Default")
      (node (ref "U$1") (pin "P$40") (pinfunction "PD8_P$40") (pintype "bidirectional"))
    )
    (net (code "104") (name "unconnected-(U$1-PD9-PadP$41)") (class "Default")
      (node (ref "U$1") (pin "P$41") (pinfunction "PD9_P$41") (pintype "bidirectional"))
    )
    (net (code "105") (name "unconnected-(U$1-PD10-PadP$42)") (class "Default")
      (node (ref "U$1") (pin "P$42") (pinfunction "PD10_P$42") (pintype "bidirectional"))
    )
    (net (code "106") (name "unconnected-(U$1-PD11-PadP$43)") (class "Default")
      (node (ref "U$1") (pin "P$43") (pinfunction "PD11_P$43") (pintype "bidirectional"))
    )
    (net (code "107") (name "unconnected-(U$1-PD12-PadP$44)") (class "Default")
      (node (ref "U$1") (pin "P$44") (pinfunction "PD12_P$44") (pintype "bidirectional"))
    )
    (net (code "108") (name "unconnected-(U$1-PD13-PadP$45)") (class "Default")
      (node (ref "U$1") (pin "P$45") (pinfunction "PD13_P$45") (pintype "bidirectional"))
    )
    (net (code "109") (name "unconnected-(U$1-PD14-PadP$46)") (class "Default")
      (node (ref "U$1") (pin "P$46") (pinfunction "PD14_P$46") (pintype "bidirectional"))
    )
    (net (code "110") (name "unconnected-(U$1-PD15-PadP$47)") (class "Default")
      (node (ref "U$1") (pin "P$47") (pinfunction "PD15_P$47") (pintype "bidirectional"))
    )
    (net (code "111") (name "unconnected-(U$1-PE12-PadP$30)") (class "Default")
      (node (ref "U$1") (pin "P$30") (pinfunction "PE12_P$30") (pintype "bidirectional"))
    )
    (net (code "112") (name "unconnected-(U$1-PE14-PadP$32)") (class "Default")
      (node (ref "U$1") (pin "P$32") (pinfunction "PE14_P$32") (pintype "bidirectional"))
    )
    (net (code "113") (name "unconnected-(U$1-PE15-PadP$33)") (class "Default")
      (node (ref "U$1") (pin "P$33") (pinfunction "PE15_P$33") (pintype "bidirectional"))
    )
    (net (code "114") (name "unconnected-(U$1-PH0-PadP$57)") (class "Default")
      (node (ref "U$1") (pin "P$57") (pinfunction "PH0_P$57") (pintype "bidirectional"))
    )
    (net (code "115") (name "unconnected-(U$1-PH1-PadP$58)") (class "Default")
      (node (ref "U$1") (pin "P$58") (pinfunction "PH1_P$58") (pintype "bidirectional"))
    )
    (net (code "116") (name "unconnected-(U$1-VDD-PadP$3)") (class "Default")
      (node (ref "U$1") (pin "P$3") (pinfunction "VDD_P$3") (pintype "bidirectional"))
    )
    (net (code "117") (name "unconnected-(U$1-VDD1-PadP$4)") (class "Default")
      (node (ref "U$1") (pin "P$4") (pinfunction "VDD1_P$4") (pintype "bidirectional"))
    )
    (net (code "118") (name "unconnected-(U$1-VDD4-PadP$72)") (class "Default")
      (node (ref "U$1") (pin "P$72") (pinfunction "VDD4_P$72") (pintype "bidirectional"))
    )
    (net (code "119") (name "unconnected-(U$3-PadBAT)") (class "Default")
      (node (ref "U$3") (pin "BAT") (pinfunction "BAT_BAT") (pintype "passive"))
    )
    (net (code "120") (name "unconnected-(U$3-PadDS1)") (class "Default")
      (node (ref "U$3") (pin "DS1") (pinfunction "DS1_DS1") (pintype "passive"))
    )
    (net (code "121") (name "unconnected-(U$3-PadDS2)") (class "Default")
      (node (ref "U$3") (pin "DS2") (pinfunction "DS2_DS2") (pintype "passive"))
    )
    (net (code "122") (name "unconnected-(U$3-PadGND2)") (class "Default")
      (node (ref "U$3") (pin "GND2") (pinfunction "GND2_GND2") (pintype "passive"))
    )
    (net (code "123") (name "unconnected-(U$3-PadSCL2)") (class "Default")
      (node (ref "U$3") (pin "SCL2") (pinfunction "SCL2_SCL2") (pintype "passive"))
    )
    (net (code "124") (name "unconnected-(U$3-PadSDA2)") (class "Default")
      (node (ref "U$3") (pin "SDA2") (pinfunction "SDA2_SDA2") (pintype "passive"))
    )
    (net (code "125") (name "unconnected-(U$3-PadSQ)") (class "Default")
      (node (ref "U$3") (pin "SQ") (pinfunction "SQ_SQ") (pintype "passive"))
    )
    (net (code "126") (name "unconnected-(U$3-PadVCC2)") (class "Default")
      (node (ref "U$3") (pin "VCC2") (pinfunction "VCC2_VCC2") (pintype "passive"))
    )
    (net (code "127") (name "unconnected-(WIFI-ADC-Pad10)") (class "Default")
      (node (ref "WIFI") (pin "10") (pinfunction "ADC_10") (pintype "bidirectional"))
    )
    (net (code "128") (name "unconnected-(WIFI-GPIO4-Pad6)") (class "Default")
      (node (ref "WIFI") (pin "6") (pinfunction "GPIO4_6") (pintype "bidirectional"))
    )
    (net (code "129") (name "unconnected-(WIFI-GPIO5-Pad5)") (class "Default")
      (node (ref "WIFI") (pin "5") (pinfunction "GPIO5_5") (pintype "bidirectional"))
    )
    (net (code "130") (name "unconnected-(WIFI-GPIO16-Pad12)") (class "Default")
      (node (ref "WIFI") (pin "12") (pinfunction "GPIO16_12") (pintype "bidirectional"))
    )
  )
)
